# CW308T_EFR32MG21_SOCKET.net
KiCad netlist of a schematic drawn in Altium Designer
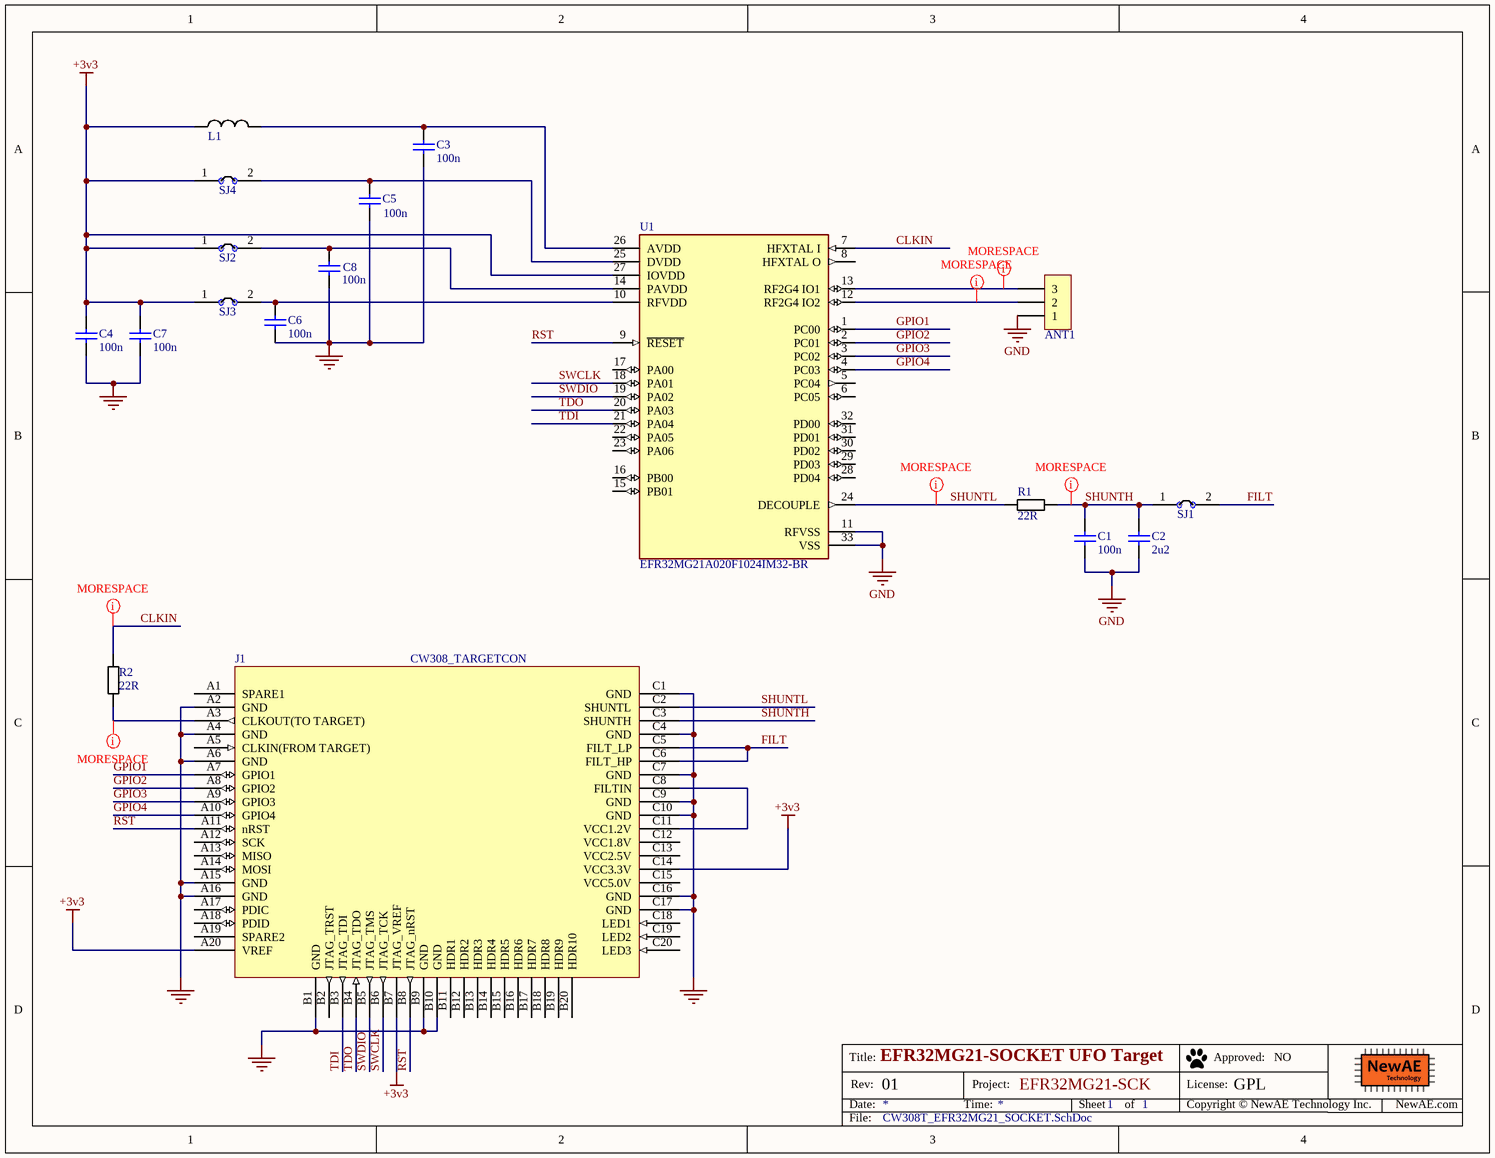
[diagram p0: CW308T_EFR32MG21_SOCKET.SchDoc]

(export (version "E")
  (design (tool "Eeschema 10.0.6"))
  (components
    (comp (ref "ANT1")
      (value "Straight Header Pins")
      (footprint "1x3_Straight_pins")
      (description "1x3 Straight pin header")
      (fields (field (name "PART NUMBER") "HDR_3PIN"))
      (libsource (lib "NewAE_AltiumLib") (part "1x3_Pin_Header"))
    )
    (comp (ref "C1")
      (value "100n")
      (footprint "CAPC0603_M")
      (description "100n, 0603")
      (fields (field (name "PART NUMBER") "CCHIP-100n-0603"))
      (libsource (lib "NewAE_AltiumLib") (part "CAP"))
    )
    (comp (ref "C2")
      (value "2u2")
      (footprint "CAPC0603_M")
      (description "2u2, 0603")
      (fields (field (name "PART NUMBER") "CCHIP-2u2-0603"))
      (libsource (lib "NewAE_AltiumLib") (part "CAP"))
    )
    (comp (ref "C3")
      (value "100n")
      (footprint "CAPC0603_M")
      (description "100n, 0603")
      (fields (field (name "PART NUMBER") "CCHIP-100n-0603"))
      (libsource (lib "NewAE_AltiumLib") (part "CAP"))
    )
    (comp (ref "C4")
      (value "100n")
      (footprint "CAPC0603_M")
      (description "100n, 0603")
      (fields (field (name "PART NUMBER") "CCHIP-100n-0603"))
      (libsource (lib "NewAE_AltiumLib") (part "CAP"))
    )
    (comp (ref "C5")
      (value "100n")
      (footprint "CAPC0603_M")
      (description "100n, 0603")
      (fields (field (name "PART NUMBER") "CCHIP-100n-0603"))
      (libsource (lib "NewAE_AltiumLib") (part "CAP"))
    )
    (comp (ref "C6")
      (value "100n")
      (footprint "CAPC0603_M")
      (description "100n, 0603")
      (fields (field (name "PART NUMBER") "CCHIP-100n-0603"))
      (libsource (lib "NewAE_AltiumLib") (part "CAP"))
    )
    (comp (ref "C7")
      (value "100n")
      (footprint "CAPC0603_M")
      (description "100n, 0603")
      (fields (field (name "PART NUMBER") "CCHIP-100n-0603"))
      (libsource (lib "NewAE_AltiumLib") (part "CAP"))
    )
    (comp (ref "C8")
      (value "100n")
      (footprint "CAPC0603_M")
      (description "100n, 0603")
      (fields (field (name "PART NUMBER") "CCHIP-100n-0603"))
      (libsource (lib "NewAE_AltiumLib") (part "CAP"))
    )
    (comp (ref "J1")
      (value "CW308_TARGETCON")
      (footprint "CW308_TBOARD_CONN")
      (description "CW308 \"Standard\" Target Board Connector")
      (fields (field (name "PART NUMBER") "CW308_TBOARD"))
      (libsource (lib "NewAE_AltiumLib") (part "CW308_TBOARD"))
    )
    (comp (ref "L1")
      (value "1k @ 1Mhz")
      (footprint "IND_0603")
      (description "Ferrite Beads HI CUR CHIP BD 0603 1000OHMS 25%")
      (fields (field (name "PART NUMBER") "FBCHIP-1k-0603"))
      (libsource (lib "NewAE_AltiumLib") (part "IND"))
    )
    (comp (ref "R1")
      (value "22R")
      (footprint "RESC1608X55N")
      (description "22R res, 0603, 1%, 1/10W")
      (fields (field (name "PART NUMBER") "RCHIP-22R-0603") (field (name "TOLERANCE") "1%"))
      (libsource (lib "") (part "RES-EU_1"))
    )
    (comp (ref "R2")
      (value "22R")
      (footprint "RESC1608X55N")
      (description "22R res, 0603, 1%, 1/10W")
      (fields (field (name "PART NUMBER") "RCHIP-22R-0603") (field (name "TOLERANCE") "1%"))
      (libsource (lib "NewAE_AltiumLib") (part "RES-EU"))
    )
    (comp (ref "SJ1")
      (value "NC")
      (footprint "SJ_2S_NC")
      (description "Solder Jumper, NC")
      (fields (field (name "PART NUMBER") "SJ_2S"))
      (libsource (lib "NewAE_AltiumLib") (part "SJ_2S"))
    )
    (comp (ref "SJ2")
      (value "NC")
      (footprint "SJ_2S_NC")
      (description "Solder Jumper, NC")
      (fields (field (name "PART NUMBER") "SJ_2S"))
      (libsource (lib "NewAE_AltiumLib") (part "SJ_2S"))
    )
    (comp (ref "SJ3")
      (value "NC")
      (footprint "SJ_2S_NC")
      (description "Solder Jumper, NC")
      (fields (field (name "PART NUMBER") "SJ_2S"))
      (libsource (lib "NewAE_AltiumLib") (part "SJ_2S"))
    )
    (comp (ref "SJ4")
      (value "NC")
      (footprint "SJ_2S_NC")
      (description "Solder Jumper, NC")
      (fields (field (name "PART NUMBER") "SJ_2S"))
      (libsource (lib "NewAE_AltiumLib") (part "SJ_2S"))
    )
    (comp (ref "U1")
      (value "EFR32MG21A020F1024IM32-BR")
      (footprint "socket-QFN32-790-62032-101")
      (description "IC MCU 2.4G 20DB MULTIPROTOCOL")
      (fields
        (field (name "MANUFACTURER") "Silicon Labs")
        (field (name "OCTOPART") "https://octopart.com/efr32mg21a020f1024im32-br-silicon+labs-98975230")
      )
      (libsource (lib "NewAE_AltiumLib") (part "b191411bf8830235ba6647a90e145a1"))
    )
  )
  (nets
    (net (code "1") (name "+3v3") (class "Default")
      (node (ref "C4") (pin "1") (pinfunction "1_1") (pintype "passive"))
      (node (ref "C7") (pin "1") (pinfunction "1_1") (pintype "passive"))
      (node (ref "J1") (pin "A20") (pinfunction "VREF_A20") (pintype "tri_state"))
      (node (ref "J1") (pin "B7") (pinfunction "JTAG_VREF_B7") (pintype "tri_state"))
      (node (ref "J1") (pin "C14") (pinfunction "VCC3.3V_C14") (pintype "power_in"))
      (node (ref "L1") (pin "1") (pinfunction "1_1") (pintype "passive"))
      (node (ref "SJ2") (pin "1") (pinfunction "1_1") (pintype "passive"))
      (node (ref "SJ3") (pin "1") (pinfunction "1_1") (pintype "passive"))
      (node (ref "SJ4") (pin "1") (pinfunction "1_1") (pintype "passive"))
      (node (ref "U1") (pin "27") (pinfunction "IOVDD_27") (pintype "power_in"))
    )
    (net (code "2") (name "/CLKIN") (class "Default")
      (node (ref "R2") (pin "1") (pinfunction "1_1") (pintype "passive"))
      (node (ref "U1") (pin "7") (pinfunction "HFXTAL_I_7") (pintype "input"))
    )
    (net (code "3") (name "/FILT") (class "Default")
      (node (ref "J1") (pin "C5") (pinfunction "FILT_LP_C5") (pintype "passive"))
      (node (ref "J1") (pin "C6") (pinfunction "FILT_HP_C6") (pintype "passive"))
      (node (ref "SJ1") (pin "2") (pinfunction "2_2") (pintype "passive"))
    )
    (net (code "4") (name "/GPIO1") (class "Default")
      (node (ref "J1") (pin "A7") (pinfunction "GPIO1_A7") (pintype "bidirectional"))
      (node (ref "U1") (pin "1") (pinfunction "PC00_1") (pintype "bidirectional"))
    )
    (net (code "5") (name "/GPIO2") (class "Default")
      (node (ref "J1") (pin "A8") (pinfunction "GPIO2_A8") (pintype "bidirectional"))
      (node (ref "U1") (pin "2") (pinfunction "PC01_2") (pintype "bidirectional"))
    )
    (net (code "6") (name "/GPIO3") (class "Default")
      (node (ref "J1") (pin "A9") (pinfunction "GPIO3_A9") (pintype "bidirectional"))
      (node (ref "U1") (pin "3") (pinfunction "PC02_3") (pintype "bidirectional"))
    )
    (net (code "7") (name "/GPIO4") (class "Default")
      (node (ref "J1") (pin "A10") (pinfunction "GPIO4_A10") (pintype "bidirectional"))
      (node (ref "U1") (pin "4") (pinfunction "PC03_4") (pintype "bidirectional"))
    )
    (net (code "8") (name "/RST") (class "Default")
      (node (ref "J1") (pin "A11") (pinfunction "nRST_A11") (pintype "bidirectional"))
      (node (ref "J1") (pin "B8") (pinfunction "JTAG_nRST_B8") (pintype "output"))
      (node (ref "U1") (pin "9") (pinfunction "~{RESET}_9") (pintype "input"))
    )
    (net (code "9") (name "/SHUNTH") (class "Default")
      (node (ref "C1") (pin "1") (pinfunction "1_1") (pintype "passive"))
      (node (ref "C2") (pin "1") (pinfunction "1_1") (pintype "passive"))
      (node (ref "J1") (pin "C3") (pinfunction "SHUNTH_C3") (pintype "passive"))
      (node (ref "R1") (pin "2") (pinfunction "2_2") (pintype "passive"))
      (node (ref "SJ1") (pin "1") (pinfunction "1_1") (pintype "passive"))
    )
    (net (code "10") (name "/SHUNTL") (class "Default")
      (node (ref "J1") (pin "C2") (pinfunction "SHUNTL_C2") (pintype "passive"))
      (node (ref "R1") (pin "1") (pinfunction "1_1") (pintype "passive"))
      (node (ref "U1") (pin "24") (pinfunction "DECOUPLE_24") (pintype "output"))
    )
    (net (code "11") (name "/SWCLK") (class "Default")
      (node (ref "J1") (pin "B6") (pinfunction "JTAG_TCK_B6") (pintype "output"))
      (node (ref "U1") (pin "18") (pinfunction "PA01_18") (pintype "bidirectional"))
    )
    (net (code "12") (name "/SWDIO") (class "Default")
      (node (ref "J1") (pin "B5") (pinfunction "JTAG_TMS_B5") (pintype "output"))
      (node (ref "U1") (pin "19") (pinfunction "PA02_19") (pintype "bidirectional"))
    )
    (net (code "13") (name "/TDI") (class "Default")
      (node (ref "J1") (pin "B3") (pinfunction "JTAG_TDI_B3") (pintype "output"))
      (node (ref "U1") (pin "21") (pinfunction "PA04_21") (pintype "bidirectional"))
    )
    (net (code "14") (name "/TDO") (class "Default")
      (node (ref "J1") (pin "B4") (pinfunction "JTAG_TDO_B4") (pintype "input"))
      (node (ref "U1") (pin "20") (pinfunction "PA03_20") (pintype "bidirectional"))
    )
    (net (code "15") (name "GND") (class "Default")
      (node (ref "ANT1") (pin "1") (pinfunction "1_1") (pintype "passive"))
      (node (ref "C1") (pin "2") (pinfunction "2_2") (pintype "passive"))
      (node (ref "C2") (pin "2") (pinfunction "2_2") (pintype "passive"))
      (node (ref "C3") (pin "2") (pinfunction "2_2") (pintype "passive"))
      (node (ref "C4") (pin "2") (pinfunction "2_2") (pintype "passive"))
      (node (ref "C5") (pin "2") (pinfunction "2_2") (pintype "passive"))
      (node (ref "C6") (pin "2") (pinfunction "2_2") (pintype "passive"))
      (node (ref "C7") (pin "2") (pinfunction "2_2") (pintype "passive"))
      (node (ref "C8") (pin "2") (pinfunction "2_2") (pintype "passive"))
      (node (ref "J1") (pin "A15") (pinfunction "GND_A15") (pintype "passive"))
      (node (ref "J1") (pin "A16") (pinfunction "GND_A16") (pintype "passive"))
      (node (ref "J1") (pin "A2") (pinfunction "GND_A2") (pintype "passive"))
      (node (ref "J1") (pin "A4") (pinfunction "GND_A4") (pintype "passive"))
      (node (ref "J1") (pin "A6") (pinfunction "GND_A6") (pintype "power_in"))
      (node (ref "J1") (pin "B1") (pinfunction "GND_B1") (pintype "passive"))
      (node (ref "J1") (pin "B10") (pinfunction "GND_B10") (pintype "passive"))
      (node (ref "J1") (pin "B9") (pinfunction "GND_B9") (pintype "passive"))
      (node (ref "J1") (pin "C1") (pinfunction "GND_C1") (pintype "power_in"))
      (node (ref "J1") (pin "C10") (pinfunction "GND_C10") (pintype "power_in"))
      (node (ref "J1") (pin "C16") (pinfunction "GND_C16") (pintype "power_in"))
      (node (ref "J1") (pin "C17") (pinfunction "GND_C17") (pintype "power_in"))
      (node (ref "J1") (pin "C4") (pinfunction "GND_C4") (pintype "power_in"))
      (node (ref "J1") (pin "C7") (pinfunction "GND_C7") (pintype "power_in"))
      (node (ref "J1") (pin "C9") (pinfunction "GND_C9") (pintype "power_in"))
      (node (ref "U1") (pin "11") (pinfunction "RFVSS_11") (pintype "power_in"))
      (node (ref "U1") (pin "33") (pinfunction "VSS_33") (pintype "power_in"))
    )
    (net (code "16") (name "Net-(J1-CLKOUT(TO_TARGET))") (class "Default")
      (node (ref "J1") (pin "A3") (pinfunction "CLKOUT(TO_TARGET)_A3") (pintype "output"))
      (node (ref "R2") (pin "2") (pinfunction "2_2") (pintype "passive"))
    )
    (net (code "17") (name "Net-(J1-FILTIN)") (class "Default")
      (node (ref "J1") (pin "C11") (pinfunction "VCC1.2V_C11") (pintype "power_in"))
      (node (ref "J1") (pin "C8") (pinfunction "FILTIN_C8") (pintype "passive"))
    )
    (net (code "18") (name "Net-(U1-AVDD)") (class "Default")
      (node (ref "C3") (pin "1") (pinfunction "1_1") (pintype "passive"))
      (node (ref "L1") (pin "2") (pinfunction "2_2") (pintype "passive"))
      (node (ref "U1") (pin "26") (pinfunction "AVDD_26") (pintype "power_in"))
    )
    (net (code "19") (name "Net-(U1-DVDD)") (class "Default")
      (node (ref "C5") (pin "1") (pinfunction "1_1") (pintype "passive"))
      (node (ref "SJ4") (pin "2") (pinfunction "2_2") (pintype "passive"))
      (node (ref "U1") (pin "25") (pinfunction "DVDD_25") (pintype "power_in"))
    )
    (net (code "20") (name "Net-(U1-PAVDD)") (class "Default")
      (node (ref "C8") (pin "1") (pinfunction "1_1") (pintype "passive"))
      (node (ref "SJ2") (pin "2") (pinfunction "2_2") (pintype "passive"))
      (node (ref "U1") (pin "14") (pinfunction "PAVDD_14") (pintype "power_in"))
    )
    (net (code "21") (name "Net-(U1-RF2G4_IO1)") (class "Default")
      (node (ref "ANT1") (pin "3") (pinfunction "3_3") (pintype "passive"))
      (node (ref "U1") (pin "13") (pinfunction "RF2G4_IO1_13") (pintype "bidirectional"))
    )
    (net (code "22") (name "Net-(U1-RF2G4_IO2)") (class "Default")
      (node (ref "ANT1") (pin "2") (pinfunction "2_2") (pintype "passive"))
      (node (ref "U1") (pin "12") (pinfunction "RF2G4_IO2_12") (pintype "bidirectional"))
    )
    (net (code "23") (name "Net-(U1-RFVDD)") (class "Default")
      (node (ref "C6") (pin "1") (pinfunction "1_1") (pintype "passive"))
      (node (ref "SJ3") (pin "2") (pinfunction "2_2") (pintype "passive"))
      (node (ref "U1") (pin "10") (pinfunction "RFVDD_10") (pintype "power_in"))
    )
    (net (code "24") (name "unconnected-(J1-CLKIN(FROM_TARGET)-PadA5)") (class "Default")
      (node (ref "J1") (pin "A5") (pinfunction "CLKIN(FROM_TARGET)_A5") (pintype "input"))
    )
    (net (code "25") (name "unconnected-(J1-HDR1-PadB11)") (class "Default")
      (node (ref "J1") (pin "B11") (pinfunction "HDR1_B11") (pintype "passive"))
    )
    (net (code "26") (name "unconnected-(J1-HDR2-PadB12)") (class "Default")
      (node (ref "J1") (pin "B12") (pinfunction "HDR2_B12") (pintype "passive"))
    )
    (net (code "27") (name "unconnected-(J1-HDR3-PadB13)") (class "Default")
      (node (ref "J1") (pin "B13") (pinfunction "HDR3_B13") (pintype "passive"))
    )
    (net (code "28") (name "unconnected-(J1-HDR4-PadB14)") (class "Default")
      (node (ref "J1") (pin "B14") (pinfunction "HDR4_B14") (pintype "passive"))
    )
    (net (code "29") (name "unconnected-(J1-HDR5-PadB15)") (class "Default")
      (node (ref "J1") (pin "B15") (pinfunction "HDR5_B15") (pintype "passive"))
    )
    (net (code "30") (name "unconnected-(J1-HDR6-PadB16)") (class "Default")
      (node (ref "J1") (pin "B16") (pinfunction "HDR6_B16") (pintype "passive"))
    )
    (net (code "31") (name "unconnected-(J1-HDR7-PadB17)") (class "Default")
      (node (ref "J1") (pin "B17") (pinfunction "HDR7_B17") (pintype "passive"))
    )
    (net (code "32") (name "unconnected-(J1-HDR8-PadB18)") (class "Default")
      (node (ref "J1") (pin "B18") (pinfunction "HDR8_B18") (pintype "passive"))
    )
    (net (code "33") (name "unconnected-(J1-HDR9-PadB19)") (class "Default")
      (node (ref "J1") (pin "B19") (pinfunction "HDR9_B19") (pintype "passive"))
    )
    (net (code "34") (name "unconnected-(J1-HDR10-PadB20)") (class "Default")
      (node (ref "J1") (pin "B20") (pinfunction "HDR10_B20") (pintype "passive"))
    )
    (net (code "35") (name "unconnected-(J1-JTAG_TRST-PadB2)") (class "Default")
      (node (ref "J1") (pin "B2") (pinfunction "JTAG_TRST_B2") (pintype "output"))
    )
    (net (code "36") (name "unconnected-(J1-LED1-PadC18)") (class "Default")
      (node (ref "J1") (pin "C18") (pinfunction "LED1_C18") (pintype "input"))
    )
    (net (code "37") (name "unconnected-(J1-LED2-PadC19)") (class "Default")
      (node (ref "J1") (pin "C19") (pinfunction "LED2_C19") (pintype "input"))
    )
    (net (code "38") (name "unconnected-(J1-LED3-PadC20)") (class "Default")
      (node (ref "J1") (pin "C20") (pinfunction "LED3_C20") (pintype "input"))
    )
    (net (code "39") (name "unconnected-(J1-MISO-PadA13)") (class "Default")
      (node (ref "J1") (pin "A13") (pinfunction "MISO_A13") (pintype "bidirectional"))
    )
    (net (code "40") (name "unconnected-(J1-MOSI-PadA14)") (class "Default")
      (node (ref "J1") (pin "A14") (pinfunction "MOSI_A14") (pintype "bidirectional"))
    )
    (net (code "41") (name "unconnected-(J1-PDIC-PadA17)") (class "Default")
      (node (ref "J1") (pin "A17") (pinfunction "PDIC_A17") (pintype "bidirectional"))
    )
    (net (code "42") (name "unconnected-(J1-PDID-PadA18)") (class "Default")
      (node (ref "J1") (pin "A18") (pinfunction "PDID_A18") (pintype "bidirectional"))
    )
    (net (code "43") (name "unconnected-(J1-SCK-PadA12)") (class "Default")
      (node (ref "J1") (pin "A12") (pinfunction "SCK_A12") (pintype "bidirectional"))
    )
    (net (code "44") (name "unconnected-(J1-SPARE1-PadA1)") (class "Default")
      (node (ref "J1") (pin "A1") (pinfunction "SPARE1_A1") (pintype "passive"))
    )
    (net (code "45") (name "unconnected-(J1-SPARE2-PadA19)") (class "Default")
      (node (ref "J1") (pin "A19") (pinfunction "SPARE2_A19") (pintype "passive"))
    )
    (net (code "46") (name "unconnected-(J1-VCC1.8V-PadC12)") (class "Default")
      (node (ref "J1") (pin "C12") (pinfunction "VCC1.8V_C12") (pintype "power_in"))
    )
    (net (code "47") (name "unconnected-(J1-VCC2.5V-PadC13)") (class "Default")
      (node (ref "J1") (pin "C13") (pinfunction "VCC2.5V_C13") (pintype "power_in"))
    )
    (net (code "48") (name "unconnected-(J1-VCC5.0V-PadC15)") (class "Default")
      (node (ref "J1") (pin "C15") (pinfunction "VCC5.0V_C15") (pintype "power_in"))
    )
    (net (code "49") (name "unconnected-(U1-HFXTAL_O-Pad8)") (class "Default")
      (node (ref "U1") (pin "8") (pinfunction "HFXTAL_O_8") (pintype "output"))
    )
    (net (code "50") (name "unconnected-(U1-PA00-Pad17)") (class "Default")
      (node (ref "U1") (pin "17") (pinfunction "PA00_17") (pintype "bidirectional"))
    )
    (net (code "51") (name "unconnected-(U1-PA05-Pad22)") (class "Default")
      (node (ref "U1") (pin "22") (pinfunction "PA05_22") (pintype "bidirectional"))
    )
    (net (code "52") (name "unconnected-(U1-PA06-Pad23)") (class "Default")
      (node (ref "U1") (pin "23") (pinfunction "PA06_23") (pintype "bidirectional"))
    )
    (net (code "53") (name "unconnected-(U1-PB00-Pad16)") (class "Default")
      (node (ref "U1") (pin "16") (pinfunction "PB00_16") (pintype "bidirectional"))
    )
    (net (code "54") (name "unconnected-(U1-PB01-Pad15)") (class "Default")
      (node (ref "U1") (pin "15") (pinfunction "PB01_15") (pintype "bidirectional"))
    )
    (net (code "55") (name "unconnected-(U1-PC04-Pad5)") (class "Default")
      (node (ref "U1") (pin "5") (pinfunction "PC04_5") (pintype "output"))
    )
    (net (code "56") (name "unconnected-(U1-PC05-Pad6)") (class "Default")
      (node (ref "U1") (pin "6") (pinfunction "PC05_6") (pintype "bidirectional"))
    )
    (net (code "57") (name "unconnected-(U1-PD00-Pad32)") (class "Default")
      (node (ref "U1") (pin "32") (pinfunction "PD00_32") (pintype "bidirectional"))
    )
    (net (code "58") (name "unconnected-(U1-PD01-Pad31)") (class "Default")
      (node (ref "U1") (pin "31") (pinfunction "PD01_31") (pintype "bidirectional"))
    )
    (net (code "59") (name "unconnected-(U1-PD02-Pad30)") (class "Default")
      (node (ref "U1") (pin "30") (pinfunction "PD02_30") (pintype "bidirectional"))
    )
    (net (code "60") (name "unconnected-(U1-PD03-Pad29)") (class "Default")
      (node (ref "U1") (pin "29") (pinfunction "PD03_29") (pintype "bidirectional"))
    )
    (net (code "61") (name "unconnected-(U1-PD04-Pad28)") (class "Default")
      (node (ref "U1") (pin "28") (pinfunction "PD04_28") (pintype "bidirectional"))
    )
  )
)
